# Manual_Override.net
KiCad netlist of a schematic drawn in Altium Designer
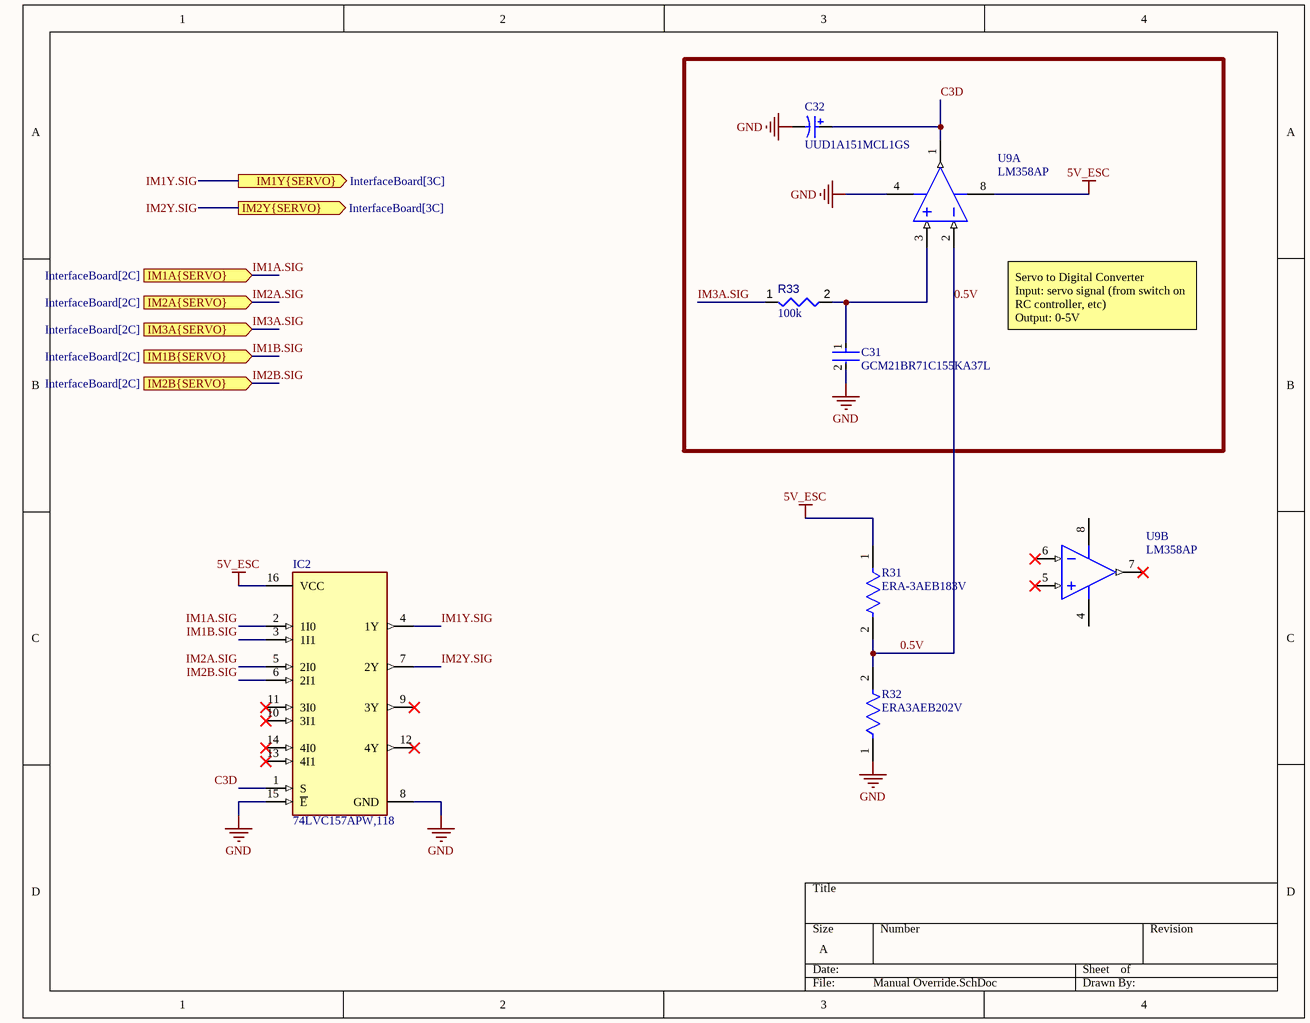
[diagram p0: Manual Override.SchDoc]

(export (version "E")
  (design (tool "Eeschema 10.0.6"))
  (components
    (comp (ref "C31")
      (value "GCM21BR71C155KA37L")
      (footprint "FP-GCM21B-0_15-IPC_B")
      (description "Ceramic Capacitor for Automotive 1.5uF ±10% 16VDC X7R 0805 Embossed T/R")
      (fields (field (name "TOLERANCE") "10%"))
      (libsource (lib "Altium Content Vault") (part "02cd4be3c70576c341d710602a673aa"))
    )
    (comp (ref "C32")
      (value "UUD1A151MCL1GS")
      (footprint "NIC-CAPA2-6.3X5.8_V")
      (fields (field (name "MANUFACTURER") "Nichicon"))
      (libsource (lib "Altium Content Vault") (part "NIC-CAP-P-2"))
    )
    (comp (ref "IC2")
      (value "74LVC157APW,118")
      (footprint "FP-SOT403-1-IPC_B")
      (description "IC QUAD 2-IN MUX 16-TSSOP")
      (libsource (lib "Altium Content Vault") (part "8840be3d548908459a661f7bc46bfcd"))
    )
    (comp (ref "R31")
      (value "ERA-3AEB183V")
      (footprint "FP-ERA3A-IPC_A")
      (description "RES SMD 18K OHM 0.1% 1/10W 0603")
      (fields (field (name "TOLERANCE") "0.1%"))
      (libsource (lib "Altium Content Vault") (part "1029c3af85768c4190bb7ad29bc67b5"))
    )
    (comp (ref "R32")
      (value "ERA3AEB202V")
      (footprint "FP-ERA3A-IPC_C")
      (description "RES SMD 2K OHM 0.1% 1/10W 0603")
      (fields (field (name "TOLERANCE") "0.1%"))
      (libsource (lib "Altium Content Vault") (part "1029c3af85768c4190bb7ad29bc67b5"))
    )
    (comp (ref "R33")
      (value "100k")
      (footprint "RESC1608X55X25ML10T15")
      (description "Chip Resistor, 100 KOhm, +/- 1%, 0.1 W, -55 to 155 degC, 0603 (1608 Metric)")
      (fields (field (name "TOLERANCE") "1%") (field (name "POWER") "100mW"))
      (libsource (lib "Isaac Lee Altium Cloud") (part "RES-2"))
    )
    (comp (ref "U9")
      (value "LM358AP")
      (footprint "P0008A")
      (description "Dual Operational Amplifier, 3 to 32 V, 0 to 70 degC, 8-Pin PDIP (P), Pb-Free (RoHS), Tube")
      (libsource (lib "Altium Content Vault") (part "TI-LM358-8"))
    )
  )
  (nets
    (net (code "1") (name "/0.5V") (class "Default")
      (node (ref "R31") (pin "2") (pinfunction "2_2") (pintype "passive"))
      (node (ref "R32") (pin "2") (pinfunction "2_2") (pintype "passive"))
      (node (ref "U9") (pin "2") (pinfunction "1IN-_2") (pintype "input"))
    )
    (net (code "2") (name "/C3D") (class "Default")
      (node (ref "C32") (pin "1") (pinfunction "1_1") (pintype "passive"))
      (node (ref "IC2") (pin "1") (pinfunction "S_1") (pintype "input"))
      (node (ref "U9") (pin "1") (pinfunction "1OUT_1") (pintype "output"))
    )
    (net (code "3") (name "/IM1A.SIG") (class "Default")
      (node (ref "IC2") (pin "2") (pinfunction "1I0_2") (pintype "input"))
    )
    (net (code "4") (name "/IM1B.SIG") (class "Default")
      (node (ref "IC2") (pin "3") (pinfunction "1I1_3") (pintype "input"))
    )
    (net (code "5") (name "/IM1Y.SIG") (class "Default")
      (node (ref "IC2") (pin "4") (pinfunction "1Y_4") (pintype "output"))
    )
    (net (code "6") (name "/IM2A.SIG") (class "Default")
      (node (ref "IC2") (pin "5") (pinfunction "2I0_5") (pintype "input"))
    )
    (net (code "7") (name "/IM2B.SIG") (class "Default")
      (node (ref "IC2") (pin "6") (pinfunction "2I1_6") (pintype "input"))
    )
    (net (code "8") (name "/IM2Y.SIG") (class "Default")
      (node (ref "IC2") (pin "7") (pinfunction "2Y_7") (pintype "output"))
    )
    (net (code "9") (name "/IM3A.SIG") (class "Default")
      (node (ref "R33") (pin "1") (pinfunction "1_1") (pintype "passive"))
    )
    (net (code "10") (name "5V_ESC") (class "Default")
      (node (ref "IC2") (pin "16") (pinfunction "VCC_16") (pintype "power_in"))
      (node (ref "R31") (pin "1") (pinfunction "1_1") (pintype "passive"))
      (node (ref "U9") (pin "8") (pinfunction "VCC_8") (pintype "power_in"))
    )
    (net (code "11") (name "GND") (class "Default")
      (node (ref "C31") (pin "2") (pinfunction "2_2") (pintype "passive"))
      (node (ref "C32") (pin "2") (pinfunction "2_2") (pintype "passive"))
      (node (ref "IC2") (pin "15") (pinfunction "~{E}_15") (pintype "input"))
      (node (ref "IC2") (pin "8") (pinfunction "GND_8") (pintype "power_in"))
      (node (ref "R32") (pin "1") (pinfunction "1_1") (pintype "passive"))
      (node (ref "U9") (pin "4") (pinfunction "GND_4") (pintype "power_in"))
    )
    (net (code "12") (name "Net-(U9A-1IN+)") (class "Default")
      (node (ref "C31") (pin "1") (pinfunction "1_1") (pintype "passive"))
      (node (ref "R33") (pin "2") (pinfunction "2_2") (pintype "passive"))
      (node (ref "U9") (pin "3") (pinfunction "1IN+_3") (pintype "input"))
    )
    (net (code "13") (name "unconnected-(IC2-3I0-Pad11)") (class "Default")
      (node (ref "IC2") (pin "11") (pinfunction "3I0_11") (pintype "input+no_connect"))
    )
    (net (code "14") (name "unconnected-(IC2-3I1-Pad10)") (class "Default")
      (node (ref "IC2") (pin "10") (pinfunction "3I1_10") (pintype "input+no_connect"))
    )
    (net (code "15") (name "unconnected-(IC2-3Y-Pad9)") (class "Default")
      (node (ref "IC2") (pin "9") (pinfunction "3Y_9") (pintype "output+no_connect"))
    )
    (net (code "16") (name "unconnected-(IC2-4I0-Pad14)") (class "Default")
      (node (ref "IC2") (pin "14") (pinfunction "4I0_14") (pintype "input+no_connect"))
    )
    (net (code "17") (name "unconnected-(IC2-4I1-Pad13)") (class "Default")
      (node (ref "IC2") (pin "13") (pinfunction "4I1_13") (pintype "input+no_connect"))
    )
    (net (code "18") (name "unconnected-(IC2-4Y-Pad12)") (class "Default")
      (node (ref "IC2") (pin "12") (pinfunction "4Y_12") (pintype "output+no_connect"))
    )
    (net (code "19") (name "unconnected-(U9B-2IN+-Pad5)") (class "Default")
      (node (ref "U9") (pin "5") (pinfunction "2IN+_5") (pintype "input+no_connect"))
    )
    (net (code "20") (name "unconnected-(U9B-2IN--Pad6)") (class "Default")
      (node (ref "U9") (pin "6") (pinfunction "2IN-_6") (pintype "input+no_connect"))
    )
    (net (code "21") (name "unconnected-(U9B-2OUT-Pad7)") (class "Default")
      (node (ref "U9") (pin "7") (pinfunction "2OUT_7") (pintype "output+no_connect"))
    )
    (net (code "22") (name "unconnected-(U9B-GND-Pad4)") (class "Default")
      (node (ref "U9") (pin "4") (pinfunction "GND_4") (pintype "power_in"))
    )
    (net (code "23") (name "unconnected-(U9B-VCC-Pad8)") (class "Default")
      (node (ref "U9") (pin "8") (pinfunction "VCC_8") (pintype "power_in"))
    )
  )
)
